# SAMV71_Xplained_Ultra_Connectors.net
KiCad netlist of a schematic drawn in Altium Designer
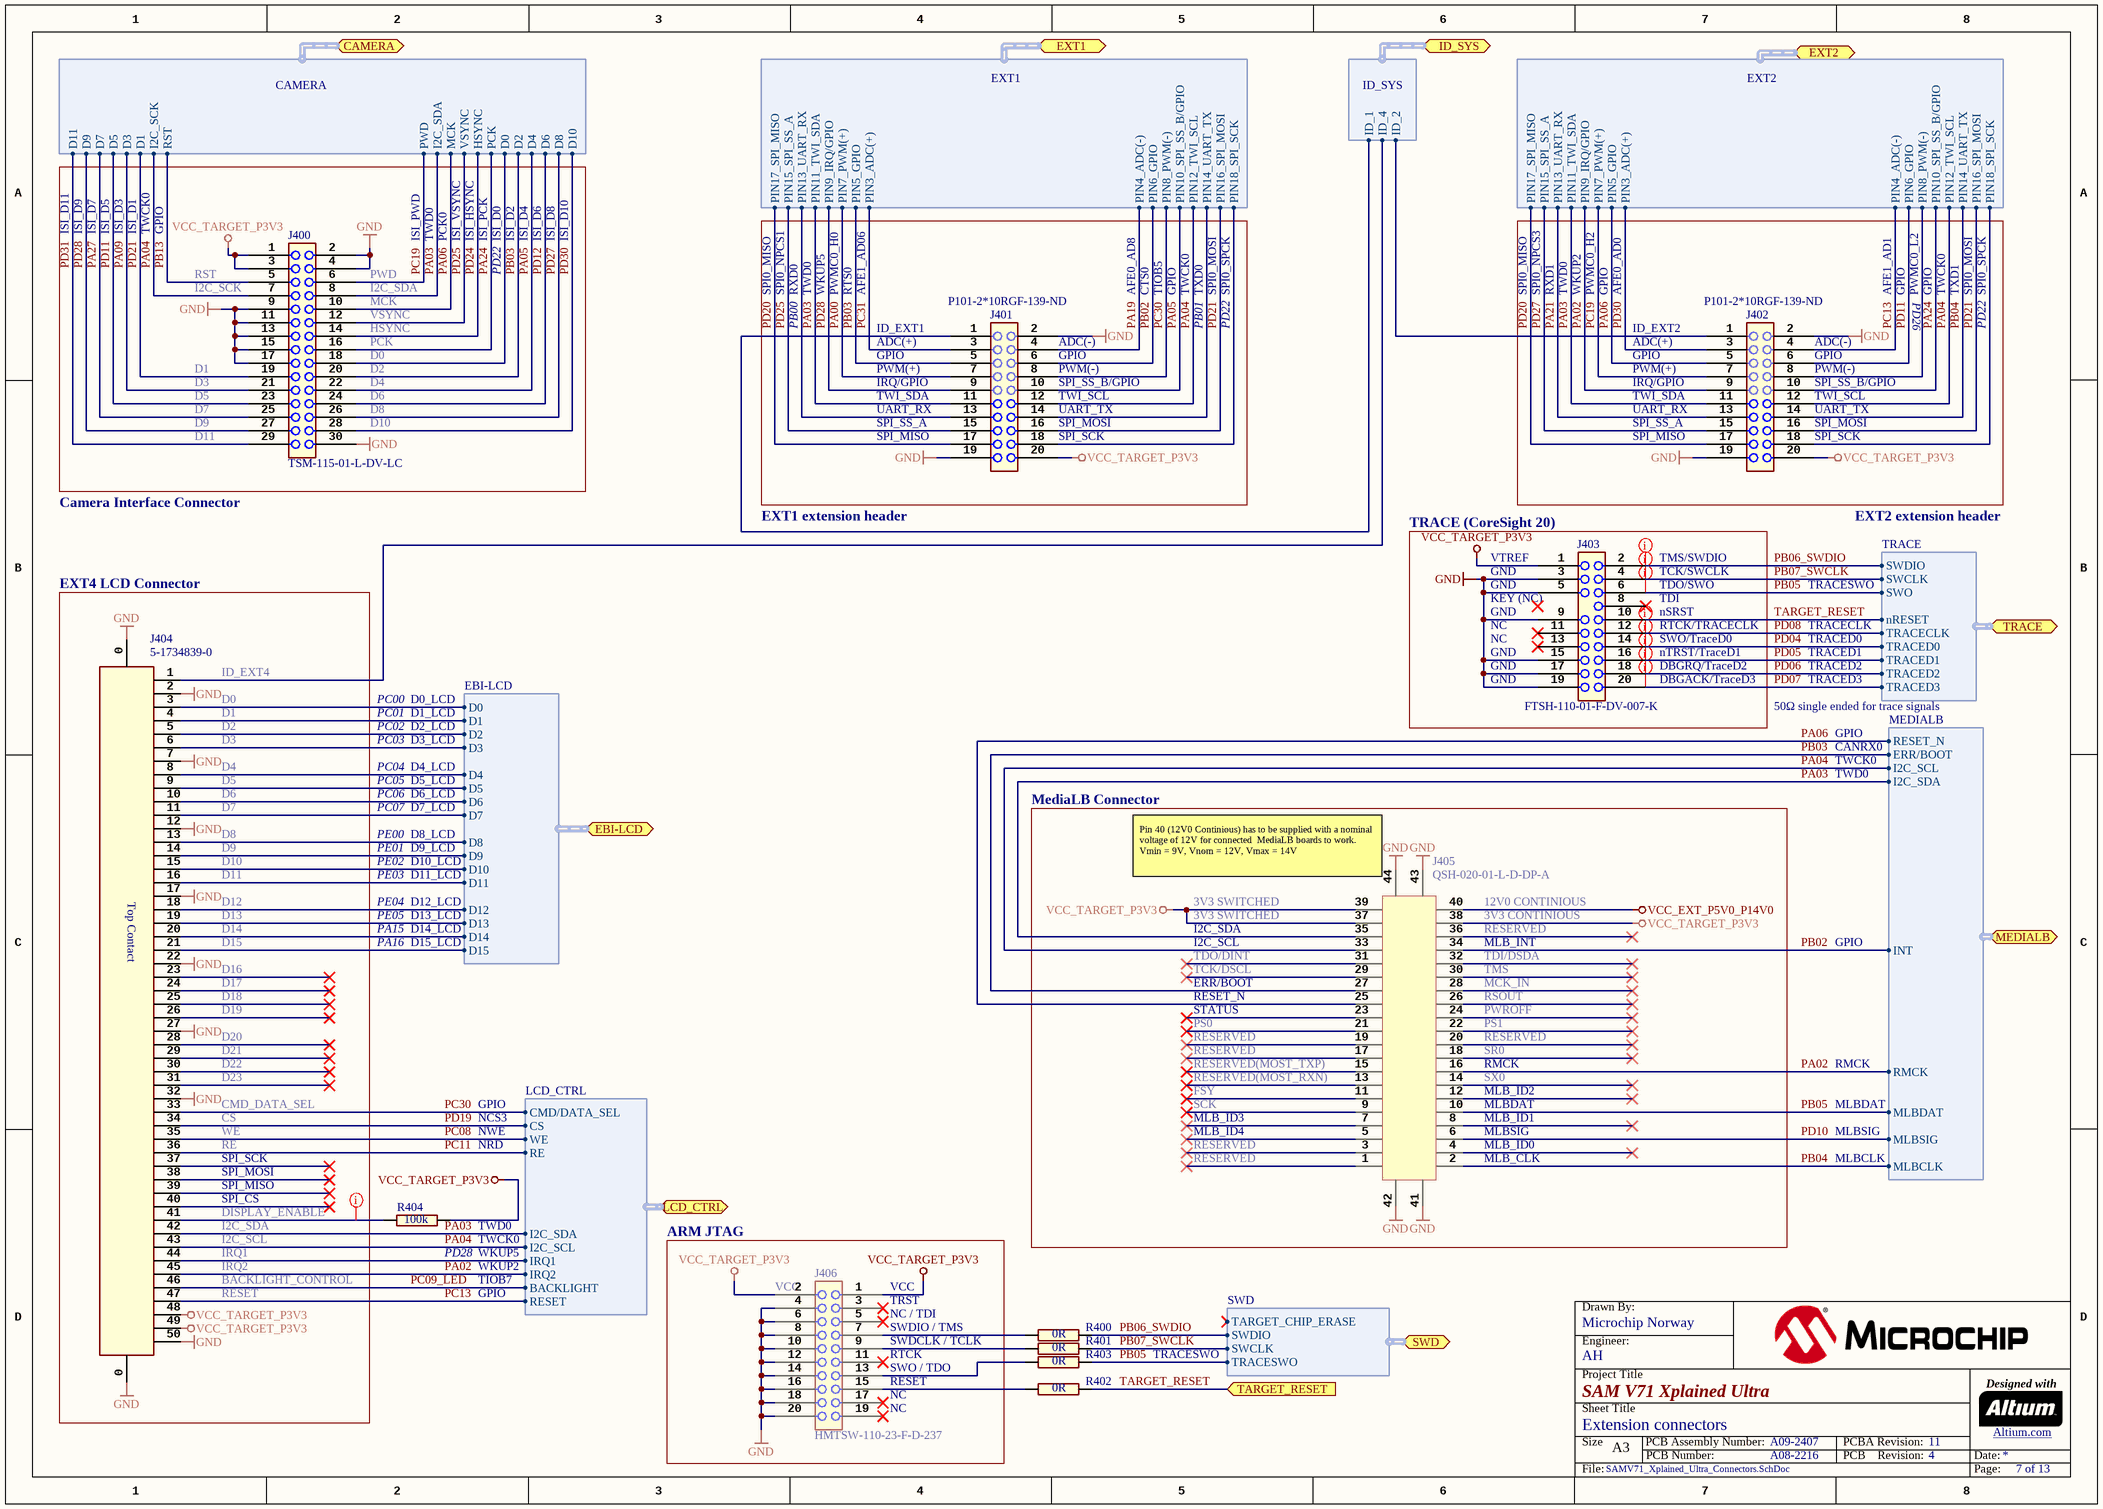
[diagram p0: SAMV71_Xplained_Ultra_Connectors.SchDoc]

(export (version "E")
  (design (tool "Eeschema 10.0.6"))
  (components
    (comp (ref "J400")
      (value "TSM-115-01-L-DV-LC")
      (footprint "AP8-00884")
      (description "Samtec TSM series, 2x15 pin header, straight, 2.54mm pitch SMD, locking leads.")
      (fields (field (name "MANUFACTURER") "SAMTEC"))
      (libsource (lib "AltiumDbLib") (part "HEADER 2x15"))
    )
    (comp (ref "J401")
      (value "P101-2*10RGF-139-ND")
      (footprint "AP8-00622")
      (description "Pin header, 2x10, Right Angle, 2.54mm, THM, Pin In Paste")
      (fields (field (name "MANUFACTURER") "Pro-data International Corp"))
      (libsource (lib "AltiumDbLib") (part "HEADER 2x10"))
    )
    (comp (ref "J402")
      (value "P101-2*10RGF-139-ND")
      (footprint "AP8-00622")
      (description "Pin header, 2x10, Right Angle, 2.54mm, THM, Pin In Paste")
      (fields (field (name "MANUFACTURER") "Pro-data International Corp"))
      (libsource (lib "AltiumDbLib") (part "HEADER 2x10"))
    )
    (comp (ref "J403")
      (value "FTSH-110-01-F-DV-007-K")
      (footprint "AP8-00910")
      (description "SAMTEC FTSH series 50-mil header, shrouded, pin 7 removed, SMD")
      (fields (field (name "MANUFACTURER") "SAMTEC"))
      (libsource (lib "AltiumDbLib") (part "FTSH-110-01-F-DV-007-K"))
    )
    (comp (ref "J404")
      (value "5-1734839-0")
      (footprint "AP8-00774")
      (description "50 pin FPC connector, e=0.5mm, single side contact (top).")
      (fields
        (field (name "MANUFACTURER") "TE Connectivity")
        (field (name "Comment") "Used for Xplained Pro MCU board on top layer.")
      )
      (libsource (lib "AltiumDbLib") (part "5-1734839-0"))
    )
    (comp (ref "J405")
      (value "QSH-020-01-L-D-DP-A")
      (footprint "AP8-00878")
      (description "SAMTEC 0.5mm, 20-pair, High-Speed Differential Pair Socket")
      (fields
        (field (name "MANUFACTURER") "SAMTEC")
        (field (name "Comment") "For SMSC MediaLB, \r\nMates with QTH-020-01-X-D-DP-XXX")
      )
      (libsource (lib "AltiumDbLib") (part "QSH-020-01-L-D-DP-A"))
    )
    (comp (ref "J406")
      (value "HMTSW-110-23-F-D-237")
      (footprint "AP8-00744")
      (description "2x10 pin header, 2.54mm pitch, Pin-in-Paste THM, 1mm hole")
      (fields (field (name "MANUFACTURER") "SAMTEC"))
      (libsource (lib "AltiumDbLib") (part "HEADER 2x10"))
    )
    (comp (ref "R400")
      (value "0R")
      (footprint "AP2-00000")
      (description "RES 0.0 OHM 1/16W 0402 SMD")
      (fields (field (name "TOLERANCE") "1 %") (field (name "MANUFACTURER") "(n/a)"))
      (libsource (lib "") (part "R2_1"))
    )
    (comp (ref "R401")
      (value "0R")
      (footprint "AP2-00000")
      (description "RES 0.0 OHM 1/16W 0402 SMD")
      (fields (field (name "TOLERANCE") "1 %") (field (name "MANUFACTURER") "(n/a)"))
      (libsource (lib "") (part "R2_1"))
    )
    (comp (ref "R402")
      (value "0R")
      (footprint "AP2-00000")
      (description "RES 0.0 OHM 1/16W 0402 SMD")
      (fields (field (name "TOLERANCE") "1 %") (field (name "MANUFACTURER") "(n/a)"))
      (libsource (lib "") (part "R2_1"))
    )
    (comp (ref "R403")
      (value "0R")
      (footprint "AP2-00000")
      (description "RES 0.0 OHM 1/16W 0402 SMD")
      (fields (field (name "TOLERANCE") "1 %") (field (name "MANUFACTURER") "(n/a)"))
      (libsource (lib "") (part "R2_1"))
    )
    (comp (ref "R404")
      (value "100k")
      (footprint "AP2-00011")
      (description "Thick film resistor, SMD 0402, 1/16W, 1%")
      (fields (field (name "TOLERANCE") "1 %") (field (name "MANUFACTURER") "ASJ"))
      (libsource (lib "AltiumDbLib") (part "R2"))
    )
  )
  (nets
    (net (code "10") (name "/D12") (class "Default")
      (node (ref "J404") (pin "18") (pinfunction "18_18") (pintype "passive"))
    )
    (net (code "11") (name "/D13") (class "Default")
      (node (ref "J404") (pin "19") (pinfunction "19_19") (pintype "passive"))
    )
    (net (code "12") (name "/D14") (class "Default")
      (node (ref "J404") (pin "20") (pinfunction "20_20") (pintype "passive"))
    )
    (net (code "13") (name "/D15") (class "Default")
      (node (ref "J404") (pin "21") (pinfunction "21_21") (pintype "passive"))
    )
    (net (code "14") (name "/ID_1") (class "Default")
      (node (ref "J401") (pin "1") (pinfunction "1_1") (pintype "passive"))
    )
    (net (code "15") (name "/ID_2") (class "Default")
      (node (ref "J402") (pin "1") (pinfunction "1_1") (pintype "passive"))
    )
    (net (code "16") (name "/ID_4") (class "Default")
      (node (ref "J404") (pin "1") (pinfunction "1_1") (pintype "passive"))
    )
    (net (code "17") (name "/IRQ1") (class "Default")
      (node (ref "J404") (pin "44") (pinfunction "44_44") (pintype "passive"))
    )
    (net (code "18") (name "/PA00") (class "Default")
      (node (ref "J401") (pin "7") (pinfunction "7_7") (pintype "passive"))
    )
    (net (code "19") (name "/PA02") (class "Default")
      (node (ref "J402") (pin "9") (pinfunction "9_9") (pintype "passive"))
      (node (ref "J404") (pin "45") (pinfunction "45_45") (pintype "passive"))
      (node (ref "J405") (pin "16") (pinfunction "16_16") (pintype "passive"))
    )
    (net (code "20") (name "/PA03") (class "Default")
      (node (ref "J400") (pin "8") (pinfunction "8_8") (pintype "passive"))
      (node (ref "J401") (pin "11") (pinfunction "11_11") (pintype "passive"))
      (node (ref "J402") (pin "11") (pinfunction "11_11") (pintype "passive"))
      (node (ref "J404") (pin "42") (pinfunction "42_42") (pintype "passive"))
      (node (ref "J405") (pin "35") (pinfunction "35_35") (pintype "passive"))
    )
    (net (code "21") (name "/PA04") (class "Default")
      (node (ref "J400") (pin "7") (pinfunction "7_7") (pintype "passive"))
      (node (ref "J401") (pin "12") (pinfunction "12_12") (pintype "passive"))
      (node (ref "J402") (pin "12") (pinfunction "12_12") (pintype "passive"))
      (node (ref "J404") (pin "43") (pinfunction "43_43") (pintype "passive"))
      (node (ref "J405") (pin "33") (pinfunction "33_33") (pintype "passive"))
    )
    (net (code "22") (name "/PA05") (class "Default")
      (node (ref "J400") (pin "22") (pinfunction "22_22") (pintype "passive"))
      (node (ref "J401") (pin "10") (pinfunction "10_10") (pintype "passive"))
    )
    (net (code "23") (name "/PA06") (class "Default")
      (node (ref "J400") (pin "10") (pinfunction "10_10") (pintype "passive"))
      (node (ref "J402") (pin "5") (pinfunction "5_5") (pintype "passive"))
      (node (ref "J405") (pin "25") (pinfunction "25_25") (pintype "passive"))
    )
    (net (code "24") (name "/PA09") (class "Default")
      (node (ref "J400") (pin "21") (pinfunction "21_21") (pintype "passive"))
    )
    (net (code "25") (name "/PA19") (class "Default")
      (node (ref "J401") (pin "4") (pinfunction "4_4") (pintype "passive"))
    )
    (net (code "26") (name "/PA21") (class "Default")
      (node (ref "J402") (pin "13") (pinfunction "13_13") (pintype "passive"))
    )
    (net (code "27") (name "/PA24") (class "Default")
      (node (ref "J400") (pin "16") (pinfunction "16_16") (pintype "passive"))
      (node (ref "J402") (pin "10") (pinfunction "10_10") (pintype "passive"))
    )
    (net (code "28") (name "/PA27") (class "Default")
      (node (ref "J400") (pin "25") (pinfunction "25_25") (pintype "passive"))
    )
    (net (code "29") (name "/PB02") (class "Default")
      (node (ref "J401") (pin "6") (pinfunction "6_6") (pintype "passive"))
      (node (ref "J405") (pin "34") (pinfunction "34_34") (pintype "passive"))
    )
    (net (code "30") (name "/PB03") (class "Default")
      (node (ref "J400") (pin "20") (pinfunction "20_20") (pintype "passive"))
      (node (ref "J401") (pin "5") (pinfunction "5_5") (pintype "passive"))
      (node (ref "J405") (pin "27") (pinfunction "27_27") (pintype "passive"))
    )
    (net (code "31") (name "/PB04") (class "Default")
      (node (ref "J402") (pin "14") (pinfunction "14_14") (pintype "passive"))
      (node (ref "J405") (pin "2") (pinfunction "2_2") (pintype "passive"))
    )
    (net (code "32") (name "/PB05") (class "Default")
      (node (ref "J403") (pin "6") (pinfunction "6_6") (pintype "passive"))
      (node (ref "J405") (pin "10") (pinfunction "10_10") (pintype "passive"))
      (node (ref "R403") (pin "2") (pinfunction "2_2") (pintype "passive"))
    )
    (net (code "33") (name "/PB06_SWDIO") (class "Default")
      (node (ref "J403") (pin "2") (pinfunction "2_2") (pintype "passive"))
      (node (ref "R400") (pin "2") (pinfunction "2_2") (pintype "passive"))
    )
    (net (code "34") (name "/PB07_SWCLK") (class "Default")
      (node (ref "J403") (pin "4") (pinfunction "4_4") (pintype "passive"))
      (node (ref "R401") (pin "2") (pinfunction "2_2") (pintype "passive"))
    )
    (net (code "35") (name "/PB13") (class "Default")
      (node (ref "J400") (pin "5") (pinfunction "5_5") (pintype "passive"))
    )
    (net (code "36") (name "/PC08") (class "Default")
      (node (ref "J404") (pin "35") (pinfunction "35_35") (pintype "passive"))
    )
    (net (code "37") (name "/PC09_LED") (class "Default")
      (node (ref "J404") (pin "46") (pinfunction "46_46") (pintype "passive"))
    )
    (net (code "38") (name "/PC11") (class "Default")
      (node (ref "J404") (pin "36") (pinfunction "36_36") (pintype "passive"))
    )
    (net (code "39") (name "/PC13") (class "Default")
      (node (ref "J402") (pin "4") (pinfunction "4_4") (pintype "passive"))
      (node (ref "J404") (pin "47") (pinfunction "47_47") (pintype "passive"))
    )
    (net (code "40") (name "/PC19") (class "Default")
      (node (ref "J400") (pin "6") (pinfunction "6_6") (pintype "passive"))
      (node (ref "J402") (pin "7") (pinfunction "7_7") (pintype "passive"))
    )
    (net (code "41") (name "/PC30") (class "Default")
      (node (ref "J401") (pin "8") (pinfunction "8_8") (pintype "passive"))
      (node (ref "J404") (pin "33") (pinfunction "33_33") (pintype "passive"))
    )
    (net (code "42") (name "/PC31") (class "Default")
      (node (ref "J401") (pin "3") (pinfunction "3_3") (pintype "passive"))
    )
    (net (code "43") (name "/PD04") (class "Default")
      (node (ref "J403") (pin "14") (pinfunction "14_14") (pintype "passive"))
    )
    (net (code "44") (name "/PD05") (class "Default")
      (node (ref "J403") (pin "16") (pinfunction "16_16") (pintype "passive"))
    )
    (net (code "45") (name "/PD06") (class "Default")
      (node (ref "J403") (pin "18") (pinfunction "18_18") (pintype "passive"))
    )
    (net (code "46") (name "/PD07") (class "Default")
      (node (ref "J403") (pin "20") (pinfunction "20_20") (pintype "passive"))
    )
    (net (code "47") (name "/PD08") (class "Default")
      (node (ref "J403") (pin "12") (pinfunction "12_12") (pintype "passive"))
    )
    (net (code "48") (name "/PD10") (class "Default")
      (node (ref "J405") (pin "6") (pinfunction "6_6") (pintype "passive"))
    )
    (net (code "49") (name "/PD11") (class "Default")
      (node (ref "J400") (pin "23") (pinfunction "23_23") (pintype "passive"))
      (node (ref "J402") (pin "6") (pinfunction "6_6") (pintype "passive"))
    )
    (net (code "50") (name "/PD12") (class "Default")
      (node (ref "J400") (pin "24") (pinfunction "24_24") (pintype "passive"))
    )
    (net (code "51") (name "/PD19") (class "Default")
      (node (ref "J404") (pin "34") (pinfunction "34_34") (pintype "passive"))
    )
    (net (code "52") (name "/PD20") (class "Default")
      (node (ref "J401") (pin "17") (pinfunction "17_17") (pintype "passive"))
      (node (ref "J402") (pin "17") (pinfunction "17_17") (pintype "passive"))
    )
    (net (code "53") (name "/PD21") (class "Default")
      (node (ref "J400") (pin "19") (pinfunction "19_19") (pintype "passive"))
      (node (ref "J401") (pin "16") (pinfunction "16_16") (pintype "passive"))
      (node (ref "J402") (pin "16") (pinfunction "16_16") (pintype "passive"))
    )
    (net (code "54") (name "/PD24") (class "Default")
      (node (ref "J400") (pin "14") (pinfunction "14_14") (pintype "passive"))
    )
    (net (code "55") (name "/PD25") (class "Default")
      (node (ref "J400") (pin "12") (pinfunction "12_12") (pintype "passive"))
      (node (ref "J401") (pin "15") (pinfunction "15_15") (pintype "passive"))
    )
    (net (code "56") (name "/PD27") (class "Default")
      (node (ref "J400") (pin "26") (pinfunction "26_26") (pintype "passive"))
      (node (ref "J402") (pin "15") (pinfunction "15_15") (pintype "passive"))
    )
    (net (code "57") (name "/PD28") (class "Default")
      (node (ref "J400") (pin "27") (pinfunction "27_27") (pintype "passive"))
      (node (ref "J401") (pin "9") (pinfunction "9_9") (pintype "passive"))
    )
    (net (code "58") (name "/PD30") (class "Default")
      (node (ref "J400") (pin "28") (pinfunction "28_28") (pintype "passive"))
      (node (ref "J402") (pin "3") (pinfunction "3_3") (pintype "passive"))
    )
    (net (code "59") (name "/PD31") (class "Default")
      (node (ref "J400") (pin "29") (pinfunction "29_29") (pintype "passive"))
    )
    (net (code "60") (name "/TARGET_RESET") (class "Default")
      (node (ref "J403") (pin "10") (pinfunction "10_10") (pintype "passive"))
      (node (ref "R402") (pin "2") (pinfunction "2_2") (pintype "passive"))
    )
    (net (code "70") (name "GND") (class "Default")
      (node (ref "J400") (pin "11") (pinfunction "11_11") (pintype "passive"))
      (node (ref "J400") (pin "13") (pinfunction "13_13") (pintype "passive"))
      (node (ref "J400") (pin "15") (pinfunction "15_15") (pintype "passive"))
      (node (ref "J400") (pin "17") (pinfunction "17_17") (pintype "passive"))
      (node (ref "J400") (pin "2") (pinfunction "2_2") (pintype "passive"))
      (node (ref "J400") (pin "30") (pinfunction "30_30") (pintype "passive"))
      (node (ref "J400") (pin "4") (pinfunction "4_4") (pintype "passive"))
      (node (ref "J400") (pin "9") (pinfunction "9_9") (pintype "passive"))
      (node (ref "J401") (pin "19") (pinfunction "19_19") (pintype "passive"))
      (node (ref "J401") (pin "2") (pinfunction "2_2") (pintype "passive"))
      (node (ref "J402") (pin "19") (pinfunction "19_19") (pintype "passive"))
      (node (ref "J402") (pin "2") (pinfunction "2_2") (pintype "passive"))
      (node (ref "J403") (pin "15") (pinfunction "15_15") (pintype "passive"))
      (node (ref "J403") (pin "17") (pinfunction "17_17") (pintype "passive"))
      (node (ref "J403") (pin "19") (pinfunction "19_19") (pintype "passive"))
      (node (ref "J403") (pin "3") (pinfunction "3_3") (pintype "passive"))
      (node (ref "J403") (pin "5") (pinfunction "5_5") (pintype "passive"))
      (node (ref "J403") (pin "9") (pinfunction "9_9") (pintype "passive"))
      (node (ref "J404") (pin "0") (pinfunction "1_0") (pintype "passive"))
      (node (ref "J404") (pin "12") (pinfunction "12_12") (pintype "passive"))
      (node (ref "J404") (pin "17") (pinfunction "17_17") (pintype "passive"))
      (node (ref "J404") (pin "2") (pinfunction "2_2") (pintype "passive"))
      (node (ref "J404") (pin "22") (pinfunction "22_22") (pintype "passive"))
      (node (ref "J404") (pin "27") (pinfunction "27_27") (pintype "passive"))
      (node (ref "J404") (pin "32") (pinfunction "32_32") (pintype "passive"))
      (node (ref "J404") (pin "50") (pinfunction "50_50") (pintype "passive"))
      (node (ref "J404") (pin "7") (pinfunction "7_7") (pintype "passive"))
      (node (ref "J405") (pin "41") (pinfunction "41_41") (pintype "passive"))
      (node (ref "J405") (pin "42") (pinfunction "42_42") (pintype "passive"))
      (node (ref "J405") (pin "43") (pinfunction "43_43") (pintype "passive"))
      (node (ref "J405") (pin "44") (pinfunction "44_44") (pintype "passive"))
      (node (ref "J406") (pin "10") (pinfunction "10_10") (pintype "passive"))
      (node (ref "J406") (pin "12") (pinfunction "12_12") (pintype "passive"))
      (node (ref "J406") (pin "14") (pinfunction "14_14") (pintype "passive"))
      (node (ref "J406") (pin "16") (pinfunction "16_16") (pintype "passive"))
      (node (ref "J406") (pin "18") (pinfunction "18_18") (pintype "passive"))
      (node (ref "J406") (pin "20") (pinfunction "20_20") (pintype "passive"))
      (node (ref "J406") (pin "4") (pinfunction "4_4") (pintype "passive"))
      (node (ref "J406") (pin "6") (pinfunction "6_6") (pintype "passive"))
      (node (ref "J406") (pin "8") (pinfunction "8_8") (pintype "passive"))
    )
    (net (code "71") (name "Net-(J404-Pad41)") (class "Default")
      (node (ref "J404") (pin "41") (pinfunction "41_41") (pintype "passive"))
      (node (ref "R404") (pin "2") (pinfunction "2_2") (pintype "passive"))
    )
    (net (code "72") (name "Net-(J406-Pad7)") (class "Default")
      (node (ref "J406") (pin "7") (pinfunction "7_7") (pintype "passive"))
      (node (ref "R400") (pin "1") (pinfunction "1_1") (pintype "passive"))
    )
    (net (code "73") (name "Net-(J406-Pad9)") (class "Default")
      (node (ref "J406") (pin "9") (pinfunction "9_9") (pintype "passive"))
      (node (ref "R401") (pin "1") (pinfunction "1_1") (pintype "passive"))
    )
    (net (code "74") (name "Net-(J406-Pad13)") (class "Default")
      (node (ref "J406") (pin "13") (pinfunction "13_13") (pintype "passive"))
      (node (ref "R403") (pin "1") (pinfunction "1_1") (pintype "passive"))
    )
    (net (code "75") (name "Net-(J406-Pad15)") (class "Default")
      (node (ref "J406") (pin "15") (pinfunction "15_15") (pintype "passive"))
      (node (ref "R402") (pin "1") (pinfunction "1_1") (pintype "passive"))
    )
    (net (code "76") (name "VCC_EXT_P5V0_P14V0") (class "Default")
      (node (ref "J405") (pin "40") (pinfunction "40_40") (pintype "passive"))
    )
    (net (code "77") (name "VCC_TARGET_P3V3") (class "Default")
      (node (ref "J400") (pin "1") (pinfunction "1_1") (pintype "passive"))
      (node (ref "J400") (pin "3") (pinfunction "3_3") (pintype "passive"))
      (node (ref "J401") (pin "20") (pinfunction "20_20") (pintype "passive"))
      (node (ref "J402") (pin "20") (pinfunction "20_20") (pintype "passive"))
      (node (ref "J403") (pin "1") (pinfunction "1_1") (pintype "passive"))
      (node (ref "J404") (pin "48") (pinfunction "48_48") (pintype "passive"))
      (node (ref "J404") (pin "49") (pinfunction "49_49") (pintype "passive"))
      (node (ref "J405") (pin "37") (pinfunction "37_37") (pintype "passive"))
      (node (ref "J405") (pin "38") (pinfunction "38_38") (pintype "passive"))
      (node (ref "J405") (pin "39") (pinfunction "39_39") (pintype "passive"))
      (node (ref "J406") (pin "1") (pinfunction "1_1") (pintype "passive"))
      (node (ref "J406") (pin "2") (pinfunction "2_2") (pintype "passive"))
      (node (ref "R404") (pin "1") (pinfunction "1_1") (pintype "passive"))
    )
    (net (code "78") (name "unconnected-(J400-Pad18)") (class "Default")
      (node (ref "J400") (pin "18") (pinfunction "18_18") (pintype "passive"))
    )
    (net (code "79") (name "unconnected-(J401-Pad13)") (class "Default")
      (node (ref "J401") (pin "13") (pinfunction "13_13") (pintype "passive"))
    )
    (net (code "80") (name "unconnected-(J401-Pad14)") (class "Default")
      (node (ref "J401") (pin "14") (pinfunction "14_14") (pintype "passive"))
    )
    (net (code "81") (name "unconnected-(J401-Pad18)") (class "Default")
      (node (ref "J401") (pin "18") (pinfunction "18_18") (pintype "passive"))
    )
    (net (code "82") (name "unconnected-(J402-Pad8)") (class "Default")
      (node (ref "J402") (pin "8") (pinfunction "8_8") (pintype "passive"))
    )
    (net (code "83") (name "unconnected-(J402-Pad18)") (class "Default")
      (node (ref "J402") (pin "18") (pinfunction "18_18") (pintype "passive"))
    )
    (net (code "84") (name "unconnected-(J403-Pad8)") (class "Default")
      (node (ref "J403") (pin "8") (pinfunction "8_8") (pintype "passive+no_connect"))
    )
    (net (code "85") (name "unconnected-(J403-Pad11)") (class "Default")
      (node (ref "J403") (pin "11") (pinfunction "11_11") (pintype "passive+no_connect"))
    )
    (net (code "86") (name "unconnected-(J403-Pad13)") (class "Default")
      (node (ref "J403") (pin "13") (pinfunction "13_13") (pintype "passive+no_connect"))
    )
    (net (code "87") (name "unconnected-(J404-Pad3)") (class "Default")
      (node (ref "J404") (pin "3") (pinfunction "3_3") (pintype "passive"))
    )
    (net (code "88") (name "unconnected-(J404-Pad4)") (class "Default")
      (node (ref "J404") (pin "4") (pinfunction "4_4") (pintype "passive"))
    )
    (net (code "89") (name "unconnected-(J404-Pad5)") (class "Default")
      (node (ref "J404") (pin "5") (pinfunction "5_5") (pintype "passive"))
    )
    (net (code "90") (name "unconnected-(J404-Pad6)") (class "Default")
      (node (ref "J404") (pin "6") (pinfunction "6_6") (pintype "passive"))
    )
    (net (code "91") (name "unconnected-(J404-Pad8)") (class "Default")
      (node (ref "J404") (pin "8") (pinfunction "8_8") (pintype "passive"))
    )
    (net (code "92") (name "unconnected-(J404-Pad9)") (class "Default")
      (node (ref "J404") (pin "9") (pinfunction "9_9") (pintype "passive"))
    )
    (net (code "93") (name "unconnected-(J404-Pad10)") (class "Default")
      (node (ref "J404") (pin "10") (pinfunction "10_10") (pintype "passive"))
    )
    (net (code "94") (name "unconnected-(J404-Pad11)") (class "Default")
      (node (ref "J404") (pin "11") (pinfunction "11_11") (pintype "passive"))
    )
    (net (code "95") (name "unconnected-(J404-Pad13)") (class "Default")
      (node (ref "J404") (pin "13") (pinfunction "13_13") (pintype "passive"))
    )
    (net (code "96") (name "unconnected-(J404-Pad14)") (class "Default")
      (node (ref "J404") (pin "14") (pinfunction "14_14") (pintype "passive"))
    )
    (net (code "97") (name "unconnected-(J404-Pad15)") (class "Default")
      (node (ref "J404") (pin "15") (pinfunction "15_15") (pintype "passive"))
    )
    (net (code "98") (name "unconnected-(J404-Pad16)") (class "Default")
      (node (ref "J404") (pin "16") (pinfunction "16_16") (pintype "passive"))
    )
    (net (code "99") (name "unconnected-(J404-Pad23)") (class "Default")
      (node (ref "J404") (pin "23") (pinfunction "23_23") (pintype "passive+no_connect"))
    )
    (net (code "100") (name "unconnected-(J404-Pad24)") (class "Default")
      (node (ref "J404") (pin "24") (pinfunction "24_24") (pintype "passive+no_connect"))
    )
    (net (code "101") (name "unconnected-(J404-Pad25)") (class "Default")
      (node (ref "J404") (pin "25") (pinfunction "25_25") (pintype "passive+no_connect"))
    )
    (net (code "102") (name "unconnected-(J404-Pad26)") (class "Default")
      (node (ref "J404") (pin "26") (pinfunction "26_26") (pintype "passive+no_connect"))
    )
    (net (code "103") (name "unconnected-(J404-Pad28)") (class "Default")
      (node (ref "J404") (pin "28") (pinfunction "28_28") (pintype "passive+no_connect"))
    )
    (net (code "104") (name "unconnected-(J404-Pad29)") (class "Default")
      (node (ref "J404") (pin "29") (pinfunction "29_29") (pintype "passive+no_connect"))
    )
    (net (code "105") (name "unconnected-(J404-Pad30)") (class "Default")
      (node (ref "J404") (pin "30") (pinfunction "30_30") (pintype "passive+no_connect"))
    )
    (net (code "106") (name "unconnected-(J404-Pad31)") (class "Default")
      (node (ref "J404") (pin "31") (pinfunction "31_31") (pintype "passive+no_connect"))
    )
    (net (code "107") (name "unconnected-(J404-Pad37)") (class "Default")
      (node (ref "J404") (pin "37") (pinfunction "37_37") (pintype "passive+no_connect"))
    )
    (net (code "108") (name "unconnected-(J404-Pad38)") (class "Default")
      (node (ref "J404") (pin "38") (pinfunction "38_38") (pintype "passive+no_connect"))
    )
    (net (code "109") (name "unconnected-(J404-Pad39)") (class "Default")
      (node (ref "J404") (pin "39") (pinfunction "39_39") (pintype "passive+no_connect"))
    )
    (net (code "110") (name "unconnected-(J404-Pad40)") (class "Default")
      (node (ref "J404") (pin "40") (pinfunction "40_40") (pintype "passive+no_connect"))
    )
    (net (code "111") (name "unconnected-(J405-Pad1)") (class "Default")
      (node (ref "J405") (pin "1") (pinfunction "1_1") (pintype "passive+no_connect"))
    )
    (net (code "112") (name "unconnected-(J405-Pad3)") (class "Default")
      (node (ref "J405") (pin "3") (pinfunction "3_3") (pintype "passive+no_connect"))
    )
    (net (code "113") (name "unconnected-(J405-Pad4)") (class "Default")
      (node (ref "J405") (pin "4") (pinfunction "4_4") (pintype "passive+no_connect"))
    )
    (net (code "114") (name "unconnected-(J405-Pad5)") (class "Default")
      (node (ref "J405") (pin "5") (pinfunction "5_5") (pintype "passive+no_connect"))
    )
    (net (code "115") (name "unconnected-(J405-Pad7)") (class "Default")
      (node (ref "J405") (pin "7") (pinfunction "7_7") (pintype "passive+no_connect"))
    )
    (net (code "116") (name "unconnected-(J405-Pad8)") (class "Default")
      (node (ref "J405") (pin "8") (pinfunction "8_8") (pintype "passive+no_connect"))
    )
    (net (code "117") (name "unconnected-(J405-Pad9)") (class "Default")
      (node (ref "J405") (pin "9") (pinfunction "9_9") (pintype "passive+no_connect"))
    )
    (net (code "118") (name "unconnected-(J405-Pad11)") (class "Default")
      (node (ref "J405") (pin "11") (pinfunction "11_11") (pintype "passive+no_connect"))
    )
    (net (code "119") (name "unconnected-(J405-Pad12)") (class "Default")
      (node (ref "J405") (pin "12") (pinfunction "12_12") (pintype "passive+no_connect"))
    )
    (net (code "120") (name "unconnected-(J405-Pad13)") (class "Default")
      (node (ref "J405") (pin "13") (pinfunction "13_13") (pintype "passive+no_connect"))
    )
    (net (code "121") (name "unconnected-(J405-Pad14)") (class "Default")
      (node (ref "J405") (pin "14") (pinfunction "14_14") (pintype "passive+no_connect"))
    )
    (net (code "122") (name "unconnected-(J405-Pad15)") (class "Default")
      (node (ref "J405") (pin "15") (pinfunction "15_15") (pintype "passive+no_connect"))
    )
    (net (code "123") (name "unconnected-(J405-Pad17)") (class "Default")
      (node (ref "J405") (pin "17") (pinfunction "17_17") (pintype "passive+no_connect"))
    )
    (net (code "124") (name "unconnected-(J405-Pad18)") (class "Default")
      (node (ref "J405") (pin "18") (pinfunction "18_18") (pintype "passive+no_connect"))
    )
    (net (code "125") (name "unconnected-(J405-Pad19)") (class "Default")
      (node (ref "J405") (pin "19") (pinfunction "19_19") (pintype "passive+no_connect"))
    )
    (net (code "126") (name "unconnected-(J405-Pad20)") (class "Default")
      (node (ref "J405") (pin "20") (pinfunction "20_20") (pintype "passive+no_connect"))
    )
    (net (code "127") (name "unconnected-(J405-Pad21)") (class "Default")
      (node (ref "J405") (pin "21") (pinfunction "21_21") (pintype "passive+no_connect"))
    )
    (net (code "128") (name "unconnected-(J405-Pad22)") (class "Default")
      (node (ref "J405") (pin "22") (pinfunction "22_22") (pintype "passive+no_connect"))
    )
    (net (code "129") (name "unconnected-(J405-Pad23)") (class "Default")
      (node (ref "J405") (pin "23") (pinfunction "23_23") (pintype "passive+no_connect"))
    )
    (net (code "130") (name "unconnected-(J405-Pad24)") (class "Default")
      (node (ref "J405") (pin "24") (pinfunction "24_24") (pintype "passive+no_connect"))
    )
    (net (code "131") (name "unconnected-(J405-Pad26)") (class "Default")
      (node (ref "J405") (pin "26") (pinfunction "26_26") (pintype "passive+no_connect"))
    )
    (net (code "132") (name "unconnected-(J405-Pad28)") (class "Default")
      (node (ref "J405") (pin "28") (pinfunction "28_28") (pintype "passive+no_connect"))
    )
    (net (code "133") (name "unconnected-(J405-Pad29)") (class "Default")
      (node (ref "J405") (pin "29") (pinfunction "29_29") (pintype "passive+no_connect"))
    )
    (net (code "134") (name "unconnected-(J405-Pad30)") (class "Default")
      (node (ref "J405") (pin "30") (pinfunction "30_30") (pintype "passive+no_connect"))
    )
    (net (code "135") (name "unconnected-(J405-Pad31)") (class "Default")
      (node (ref "J405") (pin "31") (pinfunction "31_31") (pintype "passive+no_connect"))
    )
    (net (code "136") (name "unconnected-(J405-Pad32)") (class "Default")
      (node (ref "J405") (pin "32") (pinfunction "32_32") (pintype "passive+no_connect"))
    )
    (net (code "137") (name "unconnected-(J405-Pad36)") (class "Default")
      (node (ref "J405") (pin "36") (pinfunction "36_36") (pintype "passive+no_connect"))
    )
    (net (code "138") (name "unconnected-(J406-Pad3)") (class "Default")
      (node (ref "J406") (pin "3") (pinfunction "3_3") (pintype "passive+no_connect"))
    )
    (net (code "139") (name "unconnected-(J406-Pad5)") (class "Default")
      (node (ref "J406") (pin "5") (pinfunction "5_5") (pintype "passive+no_connect"))
    )
    (net (code "140") (name "unconnected-(J406-Pad11)") (class "Default")
      (node (ref "J406") (pin "11") (pinfunction "11_11") (pintype "passive+no_connect"))
    )
    (net (code "141") (name "unconnected-(J406-Pad17)") (class "Default")
      (node (ref "J406") (pin "17") (pinfunction "17_17") (pintype "passive+no_connect"))
    )
    (net (code "142") (name "unconnected-(J406-Pad19)") (class "Default")
      (node (ref "J406") (pin "19") (pinfunction "19_19") (pintype "passive+no_connect"))
    )
  )
)
